# proLAYOUT.net
KiCad netlist of a schematic drawn in Altium Designer
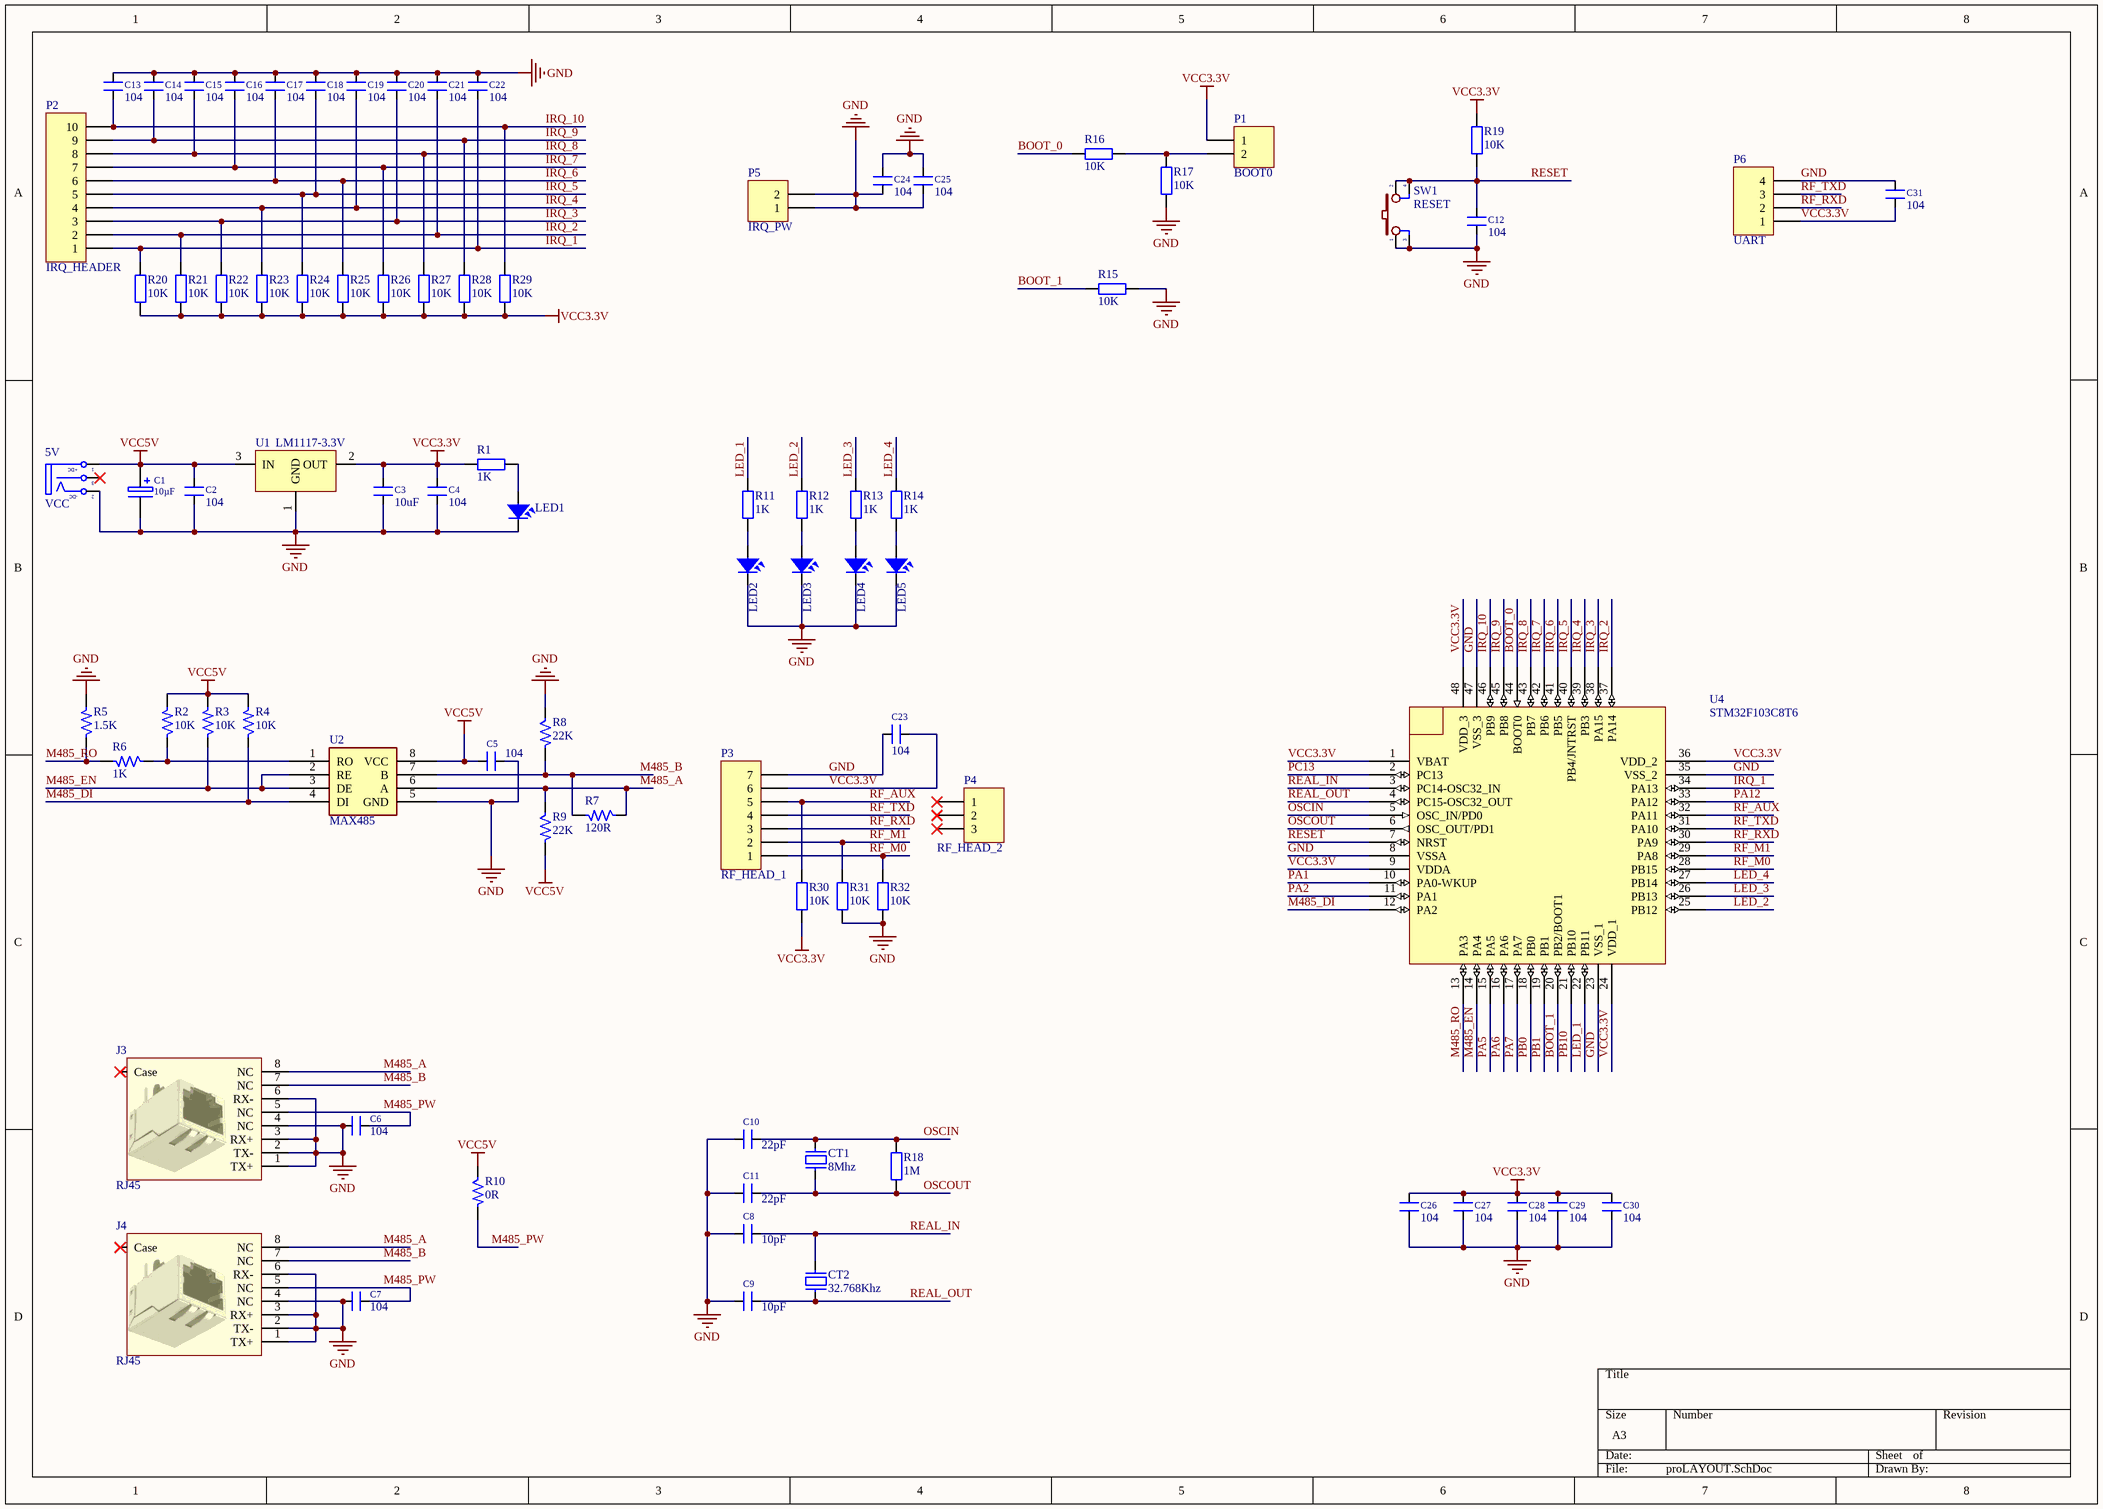
[diagram p0: proLAYOUT.SchDoc]

(export (version "E")
  (design (tool "Eeschema 10.0.6"))
  (components
    (comp (ref "C1")
      (value "10µF")
      (footprint "CAP-ALU-SMD-4.5x5x1.4")
      (fields (field (name "ALTIUM_UNNAMED_1") "10µF"))
      (libsource (lib "My library altium") (part "CAP Aluminum"))
    )
    (comp (ref "C2")
      (value "104")
      (footprint "SM-CAP-0805")
      (fields (field (name "DESIGNED BY") "VanDungEvn"))
      (libsource (lib "My library altium") (part "CAP SMD"))
    )
    (comp (ref "C3")
      (value "10uF")
      (footprint "SM-CAP-0805")
      (fields (field (name "DESIGNED BY") "VanDungEvn"))
      (libsource (lib "My library altium") (part "CAP SMD"))
    )
    (comp (ref "C4")
      (value "104")
      (footprint "SM-CAP-0805")
      (fields (field (name "DESIGNED BY") "VanDungEvn"))
      (libsource (lib "My library altium") (part "CAP SMD"))
    )
    (comp (ref "C5")
      (value "104")
      (footprint "SM-CAP-0805")
      (fields (field (name "DESIGNED BY") "VanDungEvn"))
      (libsource (lib "My library altium") (part "CAP SMD"))
    )
    (comp (ref "C6")
      (value "104")
      (footprint "SM-CAP-0805")
      (fields (field (name "DESIGNED BY") "VanDungEvn"))
      (libsource (lib "My library altium") (part "CAP SMD"))
    )
    (comp (ref "C7")
      (value "104")
      (footprint "SM-CAP-0805")
      (fields (field (name "DESIGNED BY") "VanDungEvn"))
      (libsource (lib "My library altium") (part "CAP SMD"))
    )
    (comp (ref "C8")
      (value "10pF")
      (footprint "SM-CAP-0805")
      (fields (field (name "DESIGNED BY") "VanDungEvn"))
      (libsource (lib "My library altium") (part "CAP SMD"))
    )
    (comp (ref "C9")
      (value "10pF")
      (footprint "SM-CAP-0805")
      (fields (field (name "DESIGNED BY") "VanDungEvn"))
      (libsource (lib "My library altium") (part "CAP SMD"))
    )
    (comp (ref "C10")
      (value "22pF")
      (footprint "SM-CAP-0805")
      (fields (field (name "DESIGNED BY") "VanDungEvn"))
      (libsource (lib "My library altium") (part "CAP SMD"))
    )
    (comp (ref "C11")
      (value "22pF")
      (footprint "SM-CAP-0805")
      (fields (field (name "DESIGNED BY") "VanDungEvn"))
      (libsource (lib "My library altium") (part "CAP SMD"))
    )
    (comp (ref "C12")
      (value "104")
      (footprint "SM-CAP-0805")
      (fields (field (name "DESIGNED BY") "VanDungEvn"))
      (libsource (lib "My library altium") (part "CAP SMD"))
    )
    (comp (ref "C13")
      (value "104")
      (footprint "SM-CAP-0805")
      (fields (field (name "DESIGNED BY") "VanDungEvn"))
      (libsource (lib "My library altium") (part "CAP SMD"))
    )
    (comp (ref "C14")
      (value "104")
      (footprint "SM-CAP-0805")
      (fields (field (name "DESIGNED BY") "VanDungEvn"))
      (libsource (lib "My library altium") (part "CAP SMD"))
    )
    (comp (ref "C15")
      (value "104")
      (footprint "SM-CAP-0805")
      (fields (field (name "DESIGNED BY") "VanDungEvn"))
      (libsource (lib "My library altium") (part "CAP SMD"))
    )
    (comp (ref "C16")
      (value "104")
      (footprint "SM-CAP-0805")
      (fields (field (name "DESIGNED BY") "VanDungEvn"))
      (libsource (lib "My library altium") (part "CAP SMD"))
    )
    (comp (ref "C17")
      (value "104")
      (footprint "SM-CAP-0805")
      (fields (field (name "DESIGNED BY") "VanDungEvn"))
      (libsource (lib "My library altium") (part "CAP SMD"))
    )
    (comp (ref "C18")
      (value "104")
      (footprint "SM-CAP-0805")
      (fields (field (name "DESIGNED BY") "VanDungEvn"))
      (libsource (lib "My library altium") (part "CAP SMD"))
    )
    (comp (ref "C19")
      (value "104")
      (footprint "SM-CAP-0805")
      (fields (field (name "DESIGNED BY") "VanDungEvn"))
      (libsource (lib "My library altium") (part "CAP SMD"))
    )
    (comp (ref "C20")
      (value "104")
      (footprint "SM-CAP-0805")
      (fields (field (name "DESIGNED BY") "VanDungEvn"))
      (libsource (lib "My library altium") (part "CAP SMD"))
    )
    (comp (ref "C21")
      (value "104")
      (footprint "SM-CAP-0805")
      (fields (field (name "DESIGNED BY") "VanDungEvn"))
      (libsource (lib "My library altium") (part "CAP SMD"))
    )
    (comp (ref "C22")
      (value "104")
      (footprint "SM-CAP-0805")
      (fields (field (name "DESIGNED BY") "VanDungEvn"))
      (libsource (lib "My library altium") (part "CAP SMD"))
    )
    (comp (ref "C23")
      (value "104")
      (footprint "SM-CAP-0805")
      (fields (field (name "DESIGNED BY") "VanDungEvn"))
      (libsource (lib "My library altium") (part "CAP SMD"))
    )
    (comp (ref "C24")
      (value "104")
      (footprint "SM-CAP-0805")
      (fields (field (name "DESIGNED BY") "VanDungEvn"))
      (libsource (lib "My library altium") (part "CAP SMD"))
    )
    (comp (ref "C25")
      (value "104")
      (footprint "SM-CAP-0805")
      (fields (field (name "DESIGNED BY") "VanDungEvn"))
      (libsource (lib "My library altium") (part "CAP SMD"))
    )
    (comp (ref "C26")
      (value "104")
      (footprint "SM-CAP-0805")
      (fields (field (name "DESIGNED BY") "VanDungEvn"))
      (libsource (lib "My library altium") (part "CAP SMD"))
    )
    (comp (ref "C27")
      (value "104")
      (footprint "SM-CAP-0805")
      (fields (field (name "DESIGNED BY") "VanDungEvn"))
      (libsource (lib "My library altium") (part "CAP SMD"))
    )
    (comp (ref "C28")
      (value "104")
      (footprint "SM-CAP-0805")
      (fields (field (name "DESIGNED BY") "VanDungEvn"))
      (libsource (lib "My library altium") (part "CAP SMD"))
    )
    (comp (ref "C29")
      (value "104")
      (footprint "SM-CAP-0805")
      (fields (field (name "DESIGNED BY") "VanDungEvn"))
      (libsource (lib "My library altium") (part "CAP SMD"))
    )
    (comp (ref "C30")
      (value "104")
      (footprint "SM-CAP-0805")
      (fields (field (name "DESIGNED BY") "VanDungEvn"))
      (libsource (lib "My library altium") (part "CAP SMD"))
    )
    (comp (ref "C31")
      (value "104")
      (footprint "SM-CAP-0805")
      (fields (field (name "DESIGNED BY") "VanDungEvn"))
      (libsource (lib "My library altium") (part "CAP SMD"))
    )
    (comp (ref "CT1")
      (value "8Mhz")
      (footprint "CRYSTAL_HC49-US-SM")
      (description "Crystal For all Crystal 2pin.")
      (libsource (lib "My library altium") (part "CRYSTAL"))
    )
    (comp (ref "CT2")
      (value "32.768Khz")
      (footprint "CRYSTAL SMD 32,768 kHz")
      (description "Crystal For all Crystal 2pin.")
      (libsource (lib "My library altium") (part "CRYSTAL"))
    )
    (comp (ref "J3")
      (value "RJ45")
      (footprint "RJ45 - 18")
      (description "Single RJ45 Connector Non LED")
      (libsource (lib "PART") (part "RJ45-LAN"))
    )
    (comp (ref "J4")
      (value "RJ45")
      (footprint "RJ45 - 18")
      (description "Single RJ45 Connector Non LED")
      (libsource (lib "PART") (part "RJ45-LAN"))
    )
    (comp (ref "LED1")
      (value "LED")
      (footprint "L-0805")
      (description "LED Single colour Green and Red")
      (libsource (lib "Library AL") (part "LED"))
    )
    (comp (ref "LED2")
      (value "LED")
      (footprint "L-0805")
      (description "LED Single colour Green and Red")
      (libsource (lib "Library AL") (part "LED"))
    )
    (comp (ref "LED3")
      (value "LED")
      (footprint "L-0805")
      (description "LED Single colour Green and Red")
      (libsource (lib "Library AL") (part "LED"))
    )
    (comp (ref "LED4")
      (value "LED")
      (footprint "L-0805")
      (description "LED Single colour Green and Red")
      (libsource (lib "Library AL") (part "LED"))
    )
    (comp (ref "LED5")
      (value "LED")
      (footprint "L-0805")
      (description "LED Single colour Green and Red")
      (libsource (lib "Library AL") (part "LED"))
    )
    (comp (ref "P1")
      (value "BOOT0")
      (footprint "HDR1X2")
      (description "Header, 2-Pin")
      (fields (field (name "PUBLISHER") "Altium Limited"))
      (libsource (lib "") (part "Header 2_1"))
    )
    (comp (ref "P2")
      (value "IRQ_HEADER")
      (footprint "HDR1X10")
      (description "Header, 10-Pin")
      (fields (field (name "PUBLISHER") "Altium Limited"))
      (libsource (lib "Library AL") (part "Header 10"))
    )
    (comp (ref "P3")
      (value "RF_HEAD_1")
      (footprint "HDR1X7")
      (description "Header, 7-Pin")
      (fields (field (name "PUBLISHER") "Altium Limited"))
      (libsource (lib "Library AL") (part "Header 7"))
    )
    (comp (ref "P4")
      (value "RF_HEAD_2")
      (footprint "HDR1X3")
      (description "Header, 3-Pin")
      (fields (field (name "PUBLISHER") "Altium Limited"))
      (libsource (lib "Library AL") (part "Header 3"))
    )
    (comp (ref "P5")
      (value "IRQ_PW")
      (footprint "HDR1X2")
      (description "Header, 2-Pin")
      (fields (field (name "PUBLISHER") "Altium Limited"))
      (libsource (lib "Library AL") (part "Header 2"))
    )
    (comp (ref "P6")
      (value "UART")
      (footprint "HDR1X4")
      (description "Header, 4-Pin")
      (fields (field (name "PUBLISHER") "Altium Limited"))
      (libsource (lib "Library AL") (part "Header 4"))
    )
    (comp (ref "R1")
      (value "1K")
      (footprint "SM-0805")
      (description "Resistor SMD")
      (libsource (lib "Library AL") (part "RM"))
    )
    (comp (ref "R2")
      (value "10K")
      (footprint "R-0805")
      (description "Resistor 1/4W")
      (libsource (lib "Library AL") (part "R"))
    )
    (comp (ref "R3")
      (value "10K")
      (footprint "R-0805")
      (description "Resistor 1/4W")
      (libsource (lib "Library AL") (part "R"))
    )
    (comp (ref "R4")
      (value "10K")
      (footprint "R-0805")
      (description "Resistor 1/4W")
      (libsource (lib "Library AL") (part "R"))
    )
    (comp (ref "R5")
      (value "1.5K")
      (footprint "R-0805")
      (description "Resistor 1/4W")
      (libsource (lib "Library AL") (part "R"))
    )
    (comp (ref "R6")
      (value "1K")
      (footprint "R-0805")
      (description "Resistor 1/4W")
      (libsource (lib "Library AL") (part "R"))
    )
    (comp (ref "R7")
      (value "120R")
      (footprint "R-0805")
      (description "Resistor 1/4W")
      (libsource (lib "Library AL") (part "R"))
    )
    (comp (ref "R8")
      (value "22K")
      (footprint "R-0805")
      (description "Resistor 1/4W")
      (libsource (lib "Library AL") (part "R"))
    )
    (comp (ref "R9")
      (value "22K")
      (footprint "R-0805")
      (description "Resistor 1/4W")
      (libsource (lib "Library AL") (part "R"))
    )
    (comp (ref "R10")
      (value "0R")
      (footprint "R-0805")
      (description "Resistor 1/4W")
      (libsource (lib "Library AL") (part "R"))
    )
    (comp (ref "R11")
      (value "1K")
      (footprint "SM-0805")
      (description "Resistor SMD")
      (libsource (lib "Library AL") (part "RM"))
    )
    (comp (ref "R12")
      (value "1K")
      (footprint "SM-0805")
      (description "Resistor SMD")
      (libsource (lib "Library AL") (part "RM"))
    )
    (comp (ref "R13")
      (value "1K")
      (footprint "SM-0805")
      (description "Resistor SMD")
      (libsource (lib "Library AL") (part "RM"))
    )
    (comp (ref "R14")
      (value "1K")
      (footprint "SM-0805")
      (description "Resistor SMD")
      (libsource (lib "Library AL") (part "RM"))
    )
    (comp (ref "R15")
      (value "10K")
      (footprint "SM-0805")
      (description "Resistor SMD")
      (libsource (lib "Library AL") (part "RM"))
    )
    (comp (ref "R16")
      (value "10K")
      (footprint "SM-0805")
      (description "Resistor SMD")
      (libsource (lib "Library AL") (part "RM"))
    )
    (comp (ref "R17")
      (value "10K")
      (footprint "SM-0805")
      (description "Resistor SMD")
      (libsource (lib "Library AL") (part "RM"))
    )
    (comp (ref "R18")
      (value "1M")
      (footprint "SM-0805")
      (description "Resistor SMD")
      (libsource (lib "Library AL") (part "RM"))
    )
    (comp (ref "R19")
      (value "10K")
      (footprint "SM-0805")
      (description "Resistor SMD")
      (libsource (lib "Library AL") (part "RM"))
    )
    (comp (ref "R20")
      (value "10K")
      (footprint "SM-0805")
      (description "Resistor SMD")
      (libsource (lib "Library AL") (part "RM"))
    )
    (comp (ref "R21")
      (value "10K")
      (footprint "SM-0805")
      (description "Resistor SMD")
      (libsource (lib "Library AL") (part "RM"))
    )
    (comp (ref "R22")
      (value "10K")
      (footprint "SM-0805")
      (description "Resistor SMD")
      (libsource (lib "Library AL") (part "RM"))
    )
    (comp (ref "R23")
      (value "10K")
      (footprint "SM-0805")
      (description "Resistor SMD")
      (libsource (lib "Library AL") (part "RM"))
    )
    (comp (ref "R24")
      (value "10K")
      (footprint "SM-0805")
      (description "Resistor SMD")
      (libsource (lib "Library AL") (part "RM"))
    )
    (comp (ref "R25")
      (value "10K")
      (footprint "SM-0805")
      (description "Resistor SMD")
      (libsource (lib "Library AL") (part "RM"))
    )
    (comp (ref "R26")
      (value "10K")
      (footprint "SM-0805")
      (description "Resistor SMD")
      (libsource (lib "Library AL") (part "RM"))
    )
    (comp (ref "R27")
      (value "10K")
      (footprint "SM-0805")
      (description "Resistor SMD")
      (libsource (lib "Library AL") (part "RM"))
    )
    (comp (ref "R28")
      (value "10K")
      (footprint "SM-0805")
      (description "Resistor SMD")
      (libsource (lib "Library AL") (part "RM"))
    )
    (comp (ref "R29")
      (value "10K")
      (footprint "SM-0805")
      (description "Resistor SMD")
      (libsource (lib "Library AL") (part "RM"))
    )
    (comp (ref "R30")
      (value "10K")
      (footprint "SM-0805")
      (description "Resistor SMD")
      (libsource (lib "Library AL") (part "RM"))
    )
    (comp (ref "R31")
      (value "10K")
      (footprint "SM-0805")
      (description "Resistor SMD")
      (libsource (lib "Library AL") (part "RM"))
    )
    (comp (ref "R32")
      (value "10K")
      (footprint "SM-0805")
      (description "Resistor SMD")
      (libsource (lib "Library AL") (part "RM"))
    )
    (comp (ref "SW1")
      (value "RESET")
      (footprint "SW4 CMD M")
      (description "Switch button 4 pin")
      (libsource (lib "Library AL") (part "SW4-1"))
    )
    (comp (ref "U1")
      (value "LM1117-3.3V")
      (footprint "LM1117-SOP")
      (description "800mA Low-Dropout Linear Regulator")
      (fields (field (name "CREATOR") "Nguyen Ba Bien"))
      (libsource (lib "My library altium") (part "LM1117"))
    )
    (comp (ref "U2")
      (value "MAX485")
      (footprint "SO8W_N")
      (libsource (lib "My library altium") (part "max485_smd"))
    )
    (comp (ref "U4")
      (value "STM32F103C8T6")
      (footprint "STM32_LQPF48")
      (description "STM32 ARM-based 32-bit MCU with 64 Kbytes Flash, 48-pin LQFP, Industrial Temperature")
      (fields (field (name "PUBLISHER") "Altium Limited"))
      (libsource (lib "My library altium") (part "STM32F103xx_LQFP48"))
    )
    (comp (ref "VCC") (value "5V") (footprint "DC-IN") (libsource (lib "My library altium") (part "DCIN")))
  )
  (nets
    (net (code "1") (name "/BOOT_0") (class "Default")
      (node (ref "R16") (pin "2") (pinfunction "2_2") (pintype "passive"))
      (node (ref "U4") (pin "44") (pinfunction "BOOT0_44") (pintype "input"))
    )
    (net (code "2") (name "/BOOT_1") (class "Default")
      (node (ref "R15") (pin "2") (pinfunction "2_2") (pintype "passive"))
      (node (ref "U4") (pin "20") (pinfunction "PB2/BOOT1_20") (pintype "bidirectional"))
    )
    (net (code "3") (name "/IRQ_1") (class "Default")
      (node (ref "C22") (pin "1") (pinfunction "1_1") (pintype "passive"))
      (node (ref "P2") (pin "1") (pinfunction "1_1") (pintype "passive"))
      (node (ref "R20") (pin "1") (pinfunction "1_1") (pintype "passive"))
      (node (ref "U4") (pin "34") (pinfunction "PA13_34") (pintype "bidirectional"))
    )
    (net (code "4") (name "/IRQ_2") (class "Default")
      (node (ref "C21") (pin "1") (pinfunction "1_1") (pintype "passive"))
      (node (ref "P2") (pin "2") (pinfunction "2_2") (pintype "passive"))
      (node (ref "R21") (pin "1") (pinfunction "1_1") (pintype "passive"))
      (node (ref "U4") (pin "37") (pinfunction "PA14_37") (pintype "bidirectional"))
    )
    (net (code "5") (name "/IRQ_3") (class "Default")
      (node (ref "C20") (pin "1") (pinfunction "1_1") (pintype "passive"))
      (node (ref "P2") (pin "3") (pinfunction "3_3") (pintype "passive"))
      (node (ref "R22") (pin "1") (pinfunction "1_1") (pintype "passive"))
      (node (ref "U4") (pin "38") (pinfunction "PA15_38") (pintype "bidirectional"))
    )
    (net (code "6") (name "/IRQ_4") (class "Default")
      (node (ref "C19") (pin "1") (pinfunction "1_1") (pintype "passive"))
      (node (ref "P2") (pin "4") (pinfunction "4_4") (pintype "passive"))
      (node (ref "R23") (pin "1") (pinfunction "1_1") (pintype "passive"))
      (node (ref "U4") (pin "39") (pinfunction "PB3_39") (pintype "bidirectional"))
    )
    (net (code "7") (name "/IRQ_5") (class "Default")
      (node (ref "C18") (pin "1") (pinfunction "1_1") (pintype "passive"))
      (node (ref "P2") (pin "5") (pinfunction "5_5") (pintype "passive"))
      (node (ref "R24") (pin "1") (pinfunction "1_1") (pintype "passive"))
      (node (ref "U4") (pin "40") (pinfunction "PB4/JNTRST_40") (pintype "bidirectional"))
    )
    (net (code "8") (name "/IRQ_6") (class "Default")
      (node (ref "C17") (pin "1") (pinfunction "1_1") (pintype "passive"))
      (node (ref "P2") (pin "6") (pinfunction "6_6") (pintype "passive"))
      (node (ref "R25") (pin "1") (pinfunction "1_1") (pintype "passive"))
      (node (ref "U4") (pin "41") (pinfunction "PB5_41") (pintype "bidirectional"))
    )
    (net (code "9") (name "/IRQ_7") (class "Default")
      (node (ref "C16") (pin "1") (pinfunction "1_1") (pintype "passive"))
      (node (ref "P2") (pin "7") (pinfunction "7_7") (pintype "passive"))
      (node (ref "R26") (pin "1") (pinfunction "1_1") (pintype "passive"))
      (node (ref "U4") (pin "42") (pinfunction "PB6_42") (pintype "bidirectional"))
    )
    (net (code "10") (name "/IRQ_8") (class "Default")
      (node (ref "C15") (pin "1") (pinfunction "1_1") (pintype "passive"))
      (node (ref "P2") (pin "8") (pinfunction "8_8") (pintype "passive"))
      (node (ref "R27") (pin "1") (pinfunction "1_1") (pintype "passive"))
      (node (ref "U4") (pin "43") (pinfunction "PB7_43") (pintype "bidirectional"))
    )
    (net (code "11") (name "/IRQ_9") (class "Default")
      (node (ref "C14") (pin "1") (pinfunction "1_1") (pintype "passive"))
      (node (ref "P2") (pin "9") (pinfunction "9_9") (pintype "passive"))
      (node (ref "R28") (pin "1") (pinfunction "1_1") (pintype "passive"))
      (node (ref "U4") (pin "45") (pinfunction "PB8_45") (pintype "bidirectional"))
    )
    (net (code "12") (name "/IRQ_10") (class "Default")
      (node (ref "C13") (pin "1") (pinfunction "1_1") (pintype "passive"))
      (node (ref "P2") (pin "10") (pinfunction "10_10") (pintype "passive"))
      (node (ref "R29") (pin "1") (pinfunction "1_1") (pintype "passive"))
      (node (ref "U4") (pin "46") (pinfunction "PB9_46") (pintype "bidirectional"))
    )
    (net (code "13") (name "/LED_1") (class "Default")
      (node (ref "R11") (pin "2") (pinfunction "2_2") (pintype "passive"))
      (node (ref "U4") (pin "22") (pinfunction "PB11_22") (pintype "bidirectional"))
    )
    (net (code "14") (name "/LED_2") (class "Default")
      (node (ref "R12") (pin "2") (pinfunction "2_2") (pintype "passive"))
      (node (ref "U4") (pin "25") (pinfunction "PB12_25") (pintype "bidirectional"))
    )
    (net (code "15") (name "/LED_3") (class "Default")
      (node (ref "R13") (pin "2") (pinfunction "2_2") (pintype "passive"))
      (node (ref "U4") (pin "26") (pinfunction "PB13_26") (pintype "bidirectional"))
    )
    (net (code "16") (name "/LED_4") (class "Default")
      (node (ref "R14") (pin "2") (pinfunction "2_2") (pintype "passive"))
      (node (ref "U4") (pin "27") (pinfunction "PB14_27") (pintype "bidirectional"))
    )
    (net (code "17") (name "/M485_A") (class "Default")
      (node (ref "J3") (pin "8") (pinfunction "NC_8") (pintype "passive"))
      (node (ref "J4") (pin "8") (pinfunction "NC_8") (pintype "passive"))
      (node (ref "R7") (pin "1") (pinfunction "1_1") (pintype "passive"))
      (node (ref "R9") (pin "1") (pinfunction "1_1") (pintype "passive"))
      (node (ref "U2") (pin "6") (pinfunction "A_6") (pintype "passive"))
    )
    (net (code "18") (name "/M485_B") (class "Default")
      (node (ref "J3") (pin "7") (pinfunction "NC_7") (pintype "passive"))
      (node (ref "J4") (pin "7") (pinfunction "NC_7") (pintype "passive"))
      (node (ref "R7") (pin "2") (pinfunction "2_2") (pintype "passive"))
      (node (ref "R8") (pin "2") (pinfunction "2_2") (pintype "passive"))
      (node (ref "U2") (pin "7") (pinfunction "B_7") (pintype "passive"))
    )
    (net (code "19") (name "/M485_DI") (class "Default")
      (node (ref "R4") (pin "1") (pinfunction "1_1") (pintype "passive"))
      (node (ref "U2") (pin "4") (pinfunction "DI_4") (pintype "passive"))
      (node (ref "U4") (pin "12") (pinfunction "PA2_12") (pintype "bidirectional"))
    )
    (net (code "20") (name "/M485_EN") (class "Default")
      (node (ref "R3") (pin "1") (pinfunction "1_1") (pintype "passive"))
      (node (ref "U2") (pin "2") (pinfunction "RE_2") (pintype "passive"))
      (node (ref "U2") (pin "3") (pinfunction "DE_3") (pintype "passive"))
      (node (ref "U4") (pin "14") (pinfunction "PA4_14") (pintype "bidirectional"))
    )
    (net (code "21") (name "/M485_PW") (class "Default")
      (node (ref "C6") (pin "2") (pinfunction "2_2") (pintype "passive"))
      (node (ref "C7") (pin "2") (pinfunction "2_2") (pintype "passive"))
      (node (ref "J3") (pin "5") (pinfunction "NC_5") (pintype "passive"))
      (node (ref "J4") (pin "5") (pinfunction "NC_5") (pintype "passive"))
      (node (ref "R10") (pin "2") (pinfunction "2_2") (pintype "passive"))
    )
    (net (code "22") (name "/M485_RO") (class "Default")
      (node (ref "R5") (pin "1") (pinfunction "1_1") (pintype "passive"))
      (node (ref "R6") (pin "2") (pinfunction "2_2") (pintype "passive"))
      (node (ref "U4") (pin "13") (pinfunction "PA3_13") (pintype "bidirectional"))
    )
    (net (code "23") (name "/OSCIN") (class "Default")
      (node (ref "C10") (pin "2") (pinfunction "2_2") (pintype "passive"))
      (node (ref "CT1") (pin "2") (pinfunction "2_2") (pintype "passive"))
      (node (ref "R18") (pin "1") (pinfunction "1_1") (pintype "passive"))
      (node (ref "U4") (pin "5") (pinfunction "OSC_IN/PD0_5") (pintype "input"))
    )
    (net (code "24") (name "/OSCOUT") (class "Default")
      (node (ref "C11") (pin "2") (pinfunction "2_2") (pintype "passive"))
      (node (ref "CT1") (pin "1") (pinfunction "1_1") (pintype "passive"))
      (node (ref "R18") (pin "2") (pinfunction "2_2") (pintype "passive"))
      (node (ref "U4") (pin "6") (pinfunction "OSC_OUT/PD1_6") (pintype "output"))
    )
    (net (code "25") (name "/PA1") (class "Default")
      (node (ref "U4") (pin "10") (pinfunction "PA0-WKUP_10") (pintype "bidirectional"))
    )
    (net (code "26") (name "/PA2") (class "Default")
      (node (ref "U4") (pin "11") (pinfunction "PA1_11") (pintype "bidirectional"))
    )
    (net (code "27") (name "/PA5") (class "Default")
      (node (ref "U4") (pin "15") (pinfunction "PA5_15") (pintype "bidirectional"))
    )
    (net (code "28") (name "/PA6") (class "Default")
      (node (ref "U4") (pin "16") (pinfunction "PA6_16") (pintype "bidirectional"))
    )
    (net (code "29") (name "/PA7") (class "Default")
      (node (ref "U4") (pin "17") (pinfunction "PA7_17") (pintype "bidirectional"))
    )
    (net (code "30") (name "/PA12") (class "Default")
      (node (ref "U4") (pin "33") (pinfunction "PA12_33") (pintype "bidirectional"))
    )
    (net (code "31") (name "/PB0") (class "Default")
      (node (ref "U4") (pin "18") (pinfunction "PB0_18") (pintype "bidirectional"))
    )
    (net (code "32") (name "/PB1") (class "Default")
      (node (ref "U4") (pin "19") (pinfunction "PB1_19") (pintype "bidirectional"))
    )
    (net (code "33") (name "/PB10") (class "Default")
      (node (ref "U4") (pin "21") (pinfunction "PB10_21") (pintype "bidirectional"))
    )
    (net (code "34") (name "/PC13") (class "Default")
      (node (ref "U4") (pin "2") (pinfunction "PC13_2") (pintype "bidirectional"))
    )
    (net (code "35") (name "/REAL_IN") (class "Default")
      (node (ref "C8") (pin "2") (pinfunction "2_2") (pintype "passive"))
      (node (ref "CT2") (pin "2") (pinfunction "2_2") (pintype "passive"))
      (node (ref "U4") (pin "3") (pinfunction "PC14-OSC32_IN_3") (pintype "bidirectional"))
    )
    (net (code "36") (name "/REAL_OUT") (class "Default")
      (node (ref "C9") (pin "2") (pinfunction "2_2") (pintype "passive"))
      (node (ref "CT2") (pin "1") (pinfunction "1_1") (pintype "passive"))
      (node (ref "U4") (pin "4") (pinfunction "PC15-OSC32_OUT_4") (pintype "bidirectional"))
    )
    (net (code "37") (name "/RESET") (class "Default")
      (node (ref "C12") (pin "2") (pinfunction "2_2") (pintype "passive"))
      (node (ref "R19") (pin "2") (pinfunction "2_2") (pintype "passive"))
      (node (ref "SW1") (pin "2") (pinfunction "2_2") (pintype "passive"))
      (node (ref "SW1") (pin "4") (pinfunction "4_4") (pintype "passive"))
      (node (ref "U4") (pin "7") (pinfunction "NRST_7") (pintype "bidirectional"))
    )
    (net (code "38") (name "/RF_AUX") (class "Default")
      (node (ref "P3") (pin "5") (pinfunction "5_5") (pintype "passive"))
      (node (ref "R30") (pin "1") (pinfunction "1_1") (pintype "passive"))
      (node (ref "U4") (pin "32") (pinfunction "PA11_32") (pintype "bidirectional"))
    )
    (net (code "39") (name "/RF_M0") (class "Default")
      (node (ref "P3") (pin "1") (pinfunction "1_1") (pintype "passive"))
      (node (ref "R32") (pin "1") (pinfunction "1_1") (pintype "passive"))
      (node (ref "U4") (pin "28") (pinfunction "PB15_28") (pintype "bidirectional"))
    )
    (net (code "40") (name "/RF_M1") (class "Default")
      (node (ref "P3") (pin "2") (pinfunction "2_2") (pintype "passive"))
      (node (ref "R31") (pin "1") (pinfunction "1_1") (pintype "passive"))
      (node (ref "U4") (pin "29") (pinfunction "PA8_29") (pintype "bidirectional"))
    )
    (net (code "41") (name "/RF_RXD") (class "Default")
      (node (ref "P3") (pin "3") (pinfunction "3_3") (pintype "passive"))
      (node (ref "P6") (pin "2") (pinfunction "2_2") (pintype "passive"))
      (node (ref "U4") (pin "30") (pinfunction "PA9_30") (pintype "bidirectional"))
    )
    (net (code "42") (name "/RF_TXD") (class "Default")
      (node (ref "P3") (pin "4") (pinfunction "4_4") (pintype "passive"))
      (node (ref "P6") (pin "3") (pinfunction "3_3") (pintype "passive"))
      (node (ref "U4") (pin "31") (pinfunction "PA10_31") (pintype "bidirectional"))
    )
    (net (code "43") (name "GND") (class "Default")
      (node (ref "C1") (pin "2") (pintype "passive"))
      (node (ref "C10") (pin "1") (pinfunction "1_1") (pintype "passive"))
      (node (ref "C11") (pin "1") (pinfunction "1_1") (pintype "passive"))
      (node (ref "C12") (pin "1") (pinfunction "1_1") (pintype "passive"))
      (node (ref "C13") (pin "2") (pinfunction "2_2") (pintype "passive"))
      (node (ref "C14") (pin "2") (pinfunction "2_2") (pintype "passive"))
      (node (ref "C15") (pin "2") (pinfunction "2_2") (pintype "passive"))
      (node (ref "C16") (pin "2") (pinfunction "2_2") (pintype "passive"))
      (node (ref "C17") (pin "2") (pinfunction "2_2") (pintype "passive"))
      (node (ref "C18") (pin "2") (pinfunction "2_2") (pintype "passive"))
      (node (ref "C19") (pin "2") (pinfunction "2_2") (pintype "passive"))
      (node (ref "C2") (pin "1") (pinfunction "1_1") (pintype "passive"))
      (node (ref "C20") (pin "2") (pinfunction "2_2") (pintype "passive"))
      (node (ref "C21") (pin "2") (pinfunction "2_2") (pintype "passive"))
      (node (ref "C22") (pin "2") (pinfunction "2_2") (pintype "passive"))
      (node (ref "C23") (pin "2") (pinfunction "2_2") (pintype "passive"))
      (node (ref "C24") (pin "1") (pinfunction "1_1") (pintype "passive"))
      (node (ref "C24") (pin "2") (pinfunction "2_2") (pintype "passive"))
      (node (ref "C25") (pin "1") (pinfunction "1_1") (pintype "passive"))
      (node (ref "C25") (pin "2") (pinfunction "2_2") (pintype "passive"))
      (node (ref "C26") (pin "2") (pinfunction "2_2") (pintype "passive"))
      (node (ref "C27") (pin "2") (pinfunction "2_2") (pintype "passive"))
      (node (ref "C28") (pin "2") (pinfunction "2_2") (pintype "passive"))
      (node (ref "C29") (pin "2") (pinfunction "2_2") (pintype "passive"))
      (node (ref "C3") (pin "1") (pinfunction "1_1") (pintype "passive"))
      (node (ref "C30") (pin "2") (pinfunction "2_2") (pintype "passive"))
      (node (ref "C31") (pin "2") (pinfunction "2_2") (pintype "passive"))
      (node (ref "C4") (pin "1") (pinfunction "1_1") (pintype "passive"))
      (node (ref "C5") (pin "2") (pinfunction "2_2") (pintype "passive"))
      (node (ref "C6") (pin "1") (pinfunction "1_1") (pintype "passive"))
      (node (ref "C7") (pin "1") (pinfunction "1_1") (pintype "passive"))
      (node (ref "C8") (pin "1") (pinfunction "1_1") (pintype "passive"))
      (node (ref "C9") (pin "1") (pinfunction "1_1") (pintype "passive"))
      (node (ref "J3") (pin "1") (pinfunction "TX+_1") (pintype "passive"))
      (node (ref "J3") (pin "2") (pinfunction "TX-_2") (pintype "passive"))
      (node (ref "J3") (pin "3") (pinfunction "RX+_3") (pintype "passive"))
      (node (ref "J3") (pin "4") (pinfunction "NC_4") (pintype "passive"))
      (node (ref "J3") (pin "6") (pinfunction "RX-_6") (pintype "passive"))
      (node (ref "J4") (pin "1") (pinfunction "TX+_1") (pintype "passive"))
      (node (ref "J4") (pin "2") (pinfunction "TX-_2") (pintype "passive"))
      (node (ref "J4") (pin "3") (pinfunction "RX+_3") (pintype "passive"))
      (node (ref "J4") (pin "4") (pinfunction "NC_4") (pintype "passive"))
      (node (ref "J4") (pin "6") (pinfunction "RX-_6") (pintype "passive"))
      (node (ref "LED1") (pin "2") (pinfunction "2_2") (pintype "passive"))
      (node (ref "LED2") (pin "2") (pinfunction "2_2") (pintype "passive"))
      (node (ref "LED3") (pin "2") (pinfunction "2_2") (pintype "passive"))
      (node (ref "LED4") (pin "2") (pinfunction "2_2") (pintype "passive"))
      (node (ref "LED5") (pin "2") (pinfunction "2_2") (pintype "passive"))
      (node (ref "P3") (pin "7") (pinfunction "7_7") (pintype "passive"))
      (node (ref "P5") (pin "1") (pinfunction "1_1") (pintype "passive"))
      (node (ref "P5") (pin "2") (pinfunction "2_2") (pintype "passive"))
      (node (ref "P6") (pin "4") (pinfunction "4_4") (pintype "passive"))
      (node (ref "R15") (pin "1") (pinfunction "1_1") (pintype "passive"))
      (node (ref "R17") (pin "2") (pinfunction "2_2") (pintype "passive"))
      (node (ref "R31") (pin "2") (pinfunction "2_2") (pintype "passive"))
      (node (ref "R32") (pin "2") (pinfunction "2_2") (pintype "passive"))
      (node (ref "R5") (pin "2") (pinfunction "2_2") (pintype "passive"))
      (node (ref "R8") (pin "1") (pinfunction "1_1") (pintype "passive"))
      (node (ref "SW1") (pin "1") (pinfunction "1_1") (pintype "passive"))
      (node (ref "SW1") (pin "3") (pinfunction "3_3") (pintype "passive"))
      (node (ref "U1") (pin "1") (pinfunction "GND_1") (pintype "passive"))
      (node (ref "U2") (pin "5") (pinfunction "GND_5") (pintype "passive"))
      (node (ref "U4") (pin "23") (pinfunction "VSS_1_23") (pintype "power_in"))
      (node (ref "U4") (pin "35") (pinfunction "VSS_2_35") (pintype "power_in"))
      (node (ref "U4") (pin "47") (pinfunction "VSS_3_47") (pintype "power_in"))
      (node (ref "U4") (pin "8") (pinfunction "VSSA_8") (pintype "power_in"))
      (node (ref "VCC") (pin "2") (pinfunction "TN_2") (pintype "passive"))
    )
    (net (code "44") (name "Net-(LED1-Pad1)") (class "Default")
      (node (ref "LED1") (pin "1") (pinfunction "1_1") (pintype "passive"))
      (node (ref "R1") (pin "2") (pinfunction "2_2") (pintype "passive"))
    )
    (net (code "45") (name "Net-(LED2-Pad1)") (class "Default")
      (node (ref "LED2") (pin "1") (pinfunction "1_1") (pintype "passive"))
      (node (ref "R11") (pin "1") (pinfunction "1_1") (pintype "passive"))
    )
    (net (code "46") (name "Net-(LED3-Pad1)") (class "Default")
      (node (ref "LED3") (pin "1") (pinfunction "1_1") (pintype "passive"))
      (node (ref "R12") (pin "1") (pinfunction "1_1") (pintype "passive"))
    )
    (net (code "47") (name "Net-(LED4-Pad1)") (class "Default")
      (node (ref "LED4") (pin "1") (pinfunction "1_1") (pintype "passive"))
      (node (ref "R13") (pin "1") (pinfunction "1_1") (pintype "passive"))
    )
    (net (code "48") (name "Net-(LED5-Pad1)") (class "Default")
      (node (ref "LED5") (pin "1") (pinfunction "1_1") (pintype "passive"))
      (node (ref "R14") (pin "1") (pinfunction "1_1") (pintype "passive"))
    )
    (net (code "49") (name "Net-(P1-Pad2)") (class "Default")
      (node (ref "P1") (pin "2") (pinfunction "2_2") (pintype "passive"))
      (node (ref "R16") (pin "1") (pinfunction "1_1") (pintype "passive"))
      (node (ref "R17") (pin "1") (pinfunction "1_1") (pintype "passive"))
    )
    (net (code "50") (name "Net-(U2-RO)") (class "Default")
      (node (ref "R2") (pin "1") (pinfunction "1_1") (pintype "passive"))
      (node (ref "R6") (pin "1") (pinfunction "1_1") (pintype "passive"))
      (node (ref "U2") (pin "1") (pinfunction "RO_1") (pintype "passive"))
    )
    (net (code "51") (name "VCC3.3V") (class "Default")
      (node (ref "C23") (pin "1") (pinfunction "1_1") (pintype "passive"))
      (node (ref "C26") (pin "1") (pinfunction "1_1") (pintype "passive"))
      (node (ref "C27") (pin "1") (pinfunction "1_1") (pintype "passive"))
      (node (ref "C28") (pin "1") (pinfunction "1_1") (pintype "passive"))
      (node (ref "C29") (pin "1") (pinfunction "1_1") (pintype "passive"))
      (node (ref "C3") (pin "2") (pinfunction "2_2") (pintype "passive"))
      (node (ref "C30") (pin "1") (pinfunction "1_1") (pintype "passive"))
      (node (ref "C31") (pin "1") (pinfunction "1_1") (pintype "passive"))
      (node (ref "C4") (pin "2") (pinfunction "2_2") (pintype "passive"))
      (node (ref "P1") (pin "1") (pinfunction "1_1") (pintype "passive"))
      (node (ref "P3") (pin "6") (pinfunction "6_6") (pintype "passive"))
      (node (ref "P6") (pin "1") (pinfunction "1_1") (pintype "passive"))
      (node (ref "R1") (pin "1") (pinfunction "1_1") (pintype "passive"))
      (node (ref "R19") (pin "1") (pinfunction "1_1") (pintype "passive"))
      (node (ref "R20") (pin "2") (pinfunction "2_2") (pintype "passive"))
      (node (ref "R21") (pin "2") (pinfunction "2_2") (pintype "passive"))
      (node (ref "R22") (pin "2") (pinfunction "2_2") (pintype "passive"))
      (node (ref "R23") (pin "2") (pinfunction "2_2") (pintype "passive"))
      (node (ref "R24") (pin "2") (pinfunction "2_2") (pintype "passive"))
      (node (ref "R25") (pin "2") (pinfunction "2_2") (pintype "passive"))
      (node (ref "R26") (pin "2") (pinfunction "2_2") (pintype "passive"))
      (node (ref "R27") (pin "2") (pinfunction "2_2") (pintype "passive"))
      (node (ref "R28") (pin "2") (pinfunction "2_2") (pintype "passive"))
      (node (ref "R29") (pin "2") (pinfunction "2_2") (pintype "passive"))
      (node (ref "R30") (pin "2") (pinfunction "2_2") (pintype "passive"))
      (node (ref "U1") (pin "2") (pinfunction "OUT_2") (pintype "passive"))
      (node (ref "U4") (pin "1") (pinfunction "VBAT_1") (pintype "power_in"))
      (node (ref "U4") (pin "24") (pinfunction "VDD_1_24") (pintype "power_in"))
      (node (ref "U4") (pin "36") (pinfunction "VDD_2_36") (pintype "power_in"))
      (node (ref "U4") (pin "48") (pinfunction "VDD_3_48") (pintype "power_in"))
      (node (ref "U4") (pin "9") (pinfunction "VDDA_9") (pintype "power_in"))
    )
    (net (code "52") (name "VCC5V") (class "Default")
      (node (ref "C1") (pin "1") (pintype "passive"))
      (node (ref "C2") (pin "2") (pinfunction "2_2") (pintype "passive"))
      (node (ref "C5") (pin "1") (pinfunction "1_1") (pintype "passive"))
      (node (ref "R10") (pin "1") (pinfunction "1_1") (pintype "passive"))
      (node (ref "R2") (pin "2") (pinfunction "2_2") (pintype "passive"))
      (node (ref "R3") (pin "2") (pinfunction "2_2") (pintype "passive"))
      (node (ref "R4") (pin "2") (pinfunction "2_2") (pintype "passive"))
      (node (ref "R9") (pin "2") (pinfunction "2_2") (pintype "passive"))
      (node (ref "U1") (pin "3") (pinfunction "IN_3") (pintype "passive"))
      (node (ref "U2") (pin "8") (pinfunction "VCC_8") (pintype "passive"))
      (node (ref "VCC") (pin "1") (pinfunction "T_1") (pintype "passive"))
    )
    (net (code "53") (name "unconnected-(J3-Case-Pad0)") (class "Default")
      (node (ref "J3") (pin "0") (pinfunction "Case_0") (pintype "passive+no_connect"))
    )
    (net (code "54") (name "unconnected-(J4-Case-Pad0)") (class "Default")
      (node (ref "J4") (pin "0") (pinfunction "Case_0") (pintype "passive+no_connect"))
    )
    (net (code "55") (name "unconnected-(P4-Pad1)") (class "Default")
      (node (ref "P4") (pin "1") (pinfunction "1_1") (pintype "passive+no_connect"))
    )
    (net (code "56") (name "unconnected-(P4-Pad2)") (class "Default")
      (node (ref "P4") (pin "2") (pinfunction "2_2") (pintype "passive+no_connect"))
    )
    (net (code "57") (name "unconnected-(P4-Pad3)") (class "Default")
      (node (ref "P4") (pin "3") (pinfunction "3_3") (pintype "passive+no_connect"))
    )
    (net (code "58") (name "unconnected-(VCC-S-Pad3)") (class "Default")
      (node (ref "VCC") (pin "3") (pinfunction "S_3") (pintype "power_in+no_connect"))
    )
  )
)
